# DDS_Out.net
KiCad netlist of a schematic drawn in Altium Designer
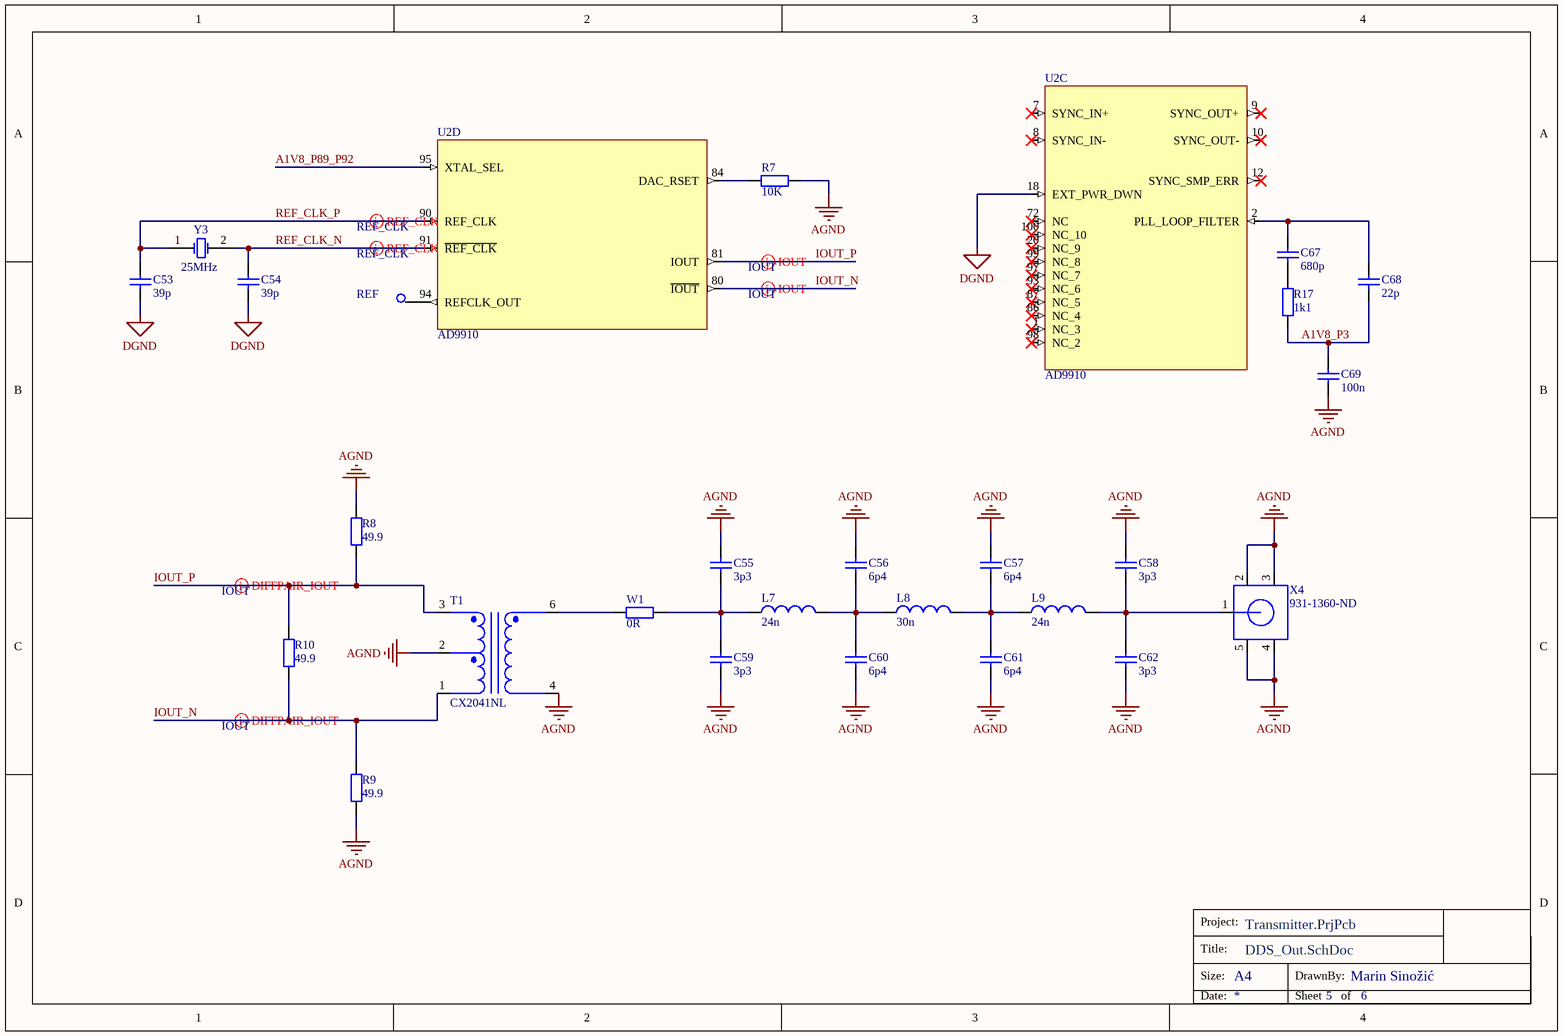
[diagram p0: DDS_Out.SchDoc]

(export (version "E")
  (design (tool "Eeschema 10.0.6"))
  (components
    (comp (ref "C53")
      (value "39p")
      (footprint "0603")
      (description "CAP CER 39PF 50V C0G/NP0 0603")
      (fields (field (name "MANUFACTURER PART NUMBER") "720-VJ0603A390GXACW1BCCT-ND"))
      (libsource (lib "Miscellaneous Devices") (part "Cap"))
    )
    (comp (ref "C54")
      (value "39p")
      (footprint "0603")
      (description "CAP CER 39PF 50V C0G/NP0 0603")
      (fields (field (name "MANUFACTURER PART NUMBER") "720-VJ0603A390GXACW1BCCT-ND"))
      (libsource (lib "Miscellaneous Devices") (part "Cap"))
    )
    (comp (ref "C55")
      (value "3p3")
      (footprint "0603")
      (description "CAP CER 3.3PF 50V C0G/NPO 0603")
      (fields (field (name "MANUFACTURER PART NUMBER") "311-3832-1-ND"))
      (libsource (lib "Tx_board") (part "C_0402_3.3pF"))
    )
    (comp (ref "C56")
      (value "6p4")
      (footprint "0603")
      (description "CAP CER RF 6.4PF 50V +/-0.1 PF C")
      (fields (field (name "MANUFACTURER PART NUMBER") "399-16225-1-ND"))
      (libsource (lib "Tx_board") (part "C_0402_6.8pF"))
    )
    (comp (ref "C57")
      (value "6p4")
      (footprint "0603")
      (description "CAP CER RF 6.4PF 50V +/-0.1 PF C")
      (fields (field (name "MANUFACTURER PART NUMBER") "399-16225-1-ND"))
      (libsource (lib "Tx_board") (part "C_0402_6.8pF"))
    )
    (comp (ref "C58")
      (value "3p3")
      (footprint "0603")
      (description "CAP CER 3.3PF 50V C0G/NPO 0603")
      (fields (field (name "MANUFACTURER PART NUMBER") "311-3832-1-ND"))
      (libsource (lib "Tx_board") (part "C_0402_3.3pF"))
    )
    (comp (ref "C59")
      (value "3p3")
      (footprint "0603")
      (description "CAP CER 3.3PF 50V C0G/NPO 0603")
      (fields (field (name "MANUFACTURER PART NUMBER") "311-3832-1-ND"))
      (libsource (lib "Tx_board") (part "C_0402_3.3pF"))
    )
    (comp (ref "C60")
      (value "6p4")
      (footprint "0603")
      (description "CAP CER RF 6.4PF 50V +/-0.1 PF C")
      (fields (field (name "MANUFACTURER PART NUMBER") "399-16225-1-ND"))
      (libsource (lib "Tx_board") (part "C_0402_6.8pF"))
    )
    (comp (ref "C61")
      (value "6p4")
      (footprint "0603")
      (description "CAP CER RF 6.4PF 50V +/-0.1 PF C")
      (fields (field (name "MANUFACTURER PART NUMBER") "399-16225-1-ND"))
      (libsource (lib "Tx_board") (part "C_0402_6.8pF"))
    )
    (comp (ref "C62")
      (value "3p3")
      (footprint "0603")
      (description "CAP CER 3.3PF 50V C0G/NPO 0603")
      (fields (field (name "MANUFACTURER PART NUMBER") "311-3832-1-ND"))
      (libsource (lib "Tx_board") (part "C_0402_3.3pF"))
    )
    (comp (ref "C67")
      (value "680p")
      (footprint "0603")
      (description "CAP CER RF 6.4PF 50V +/-0.1 PF C")
      (fields (field (name "MANUFACTURER PART NUMBER") "399-16225-1-ND"))
      (libsource (lib "Tx_board") (part "C_0402_6.8pF"))
    )
    (comp (ref "C68")
      (value "22p")
      (footprint "0603")
      (description "CAP CER RF 6.4PF 50V +/-0.1 PF C")
      (fields (field (name "MANUFACTURER PART NUMBER") "399-16225-1-ND"))
      (libsource (lib "Tx_board") (part "C_0402_6.8pF"))
    )
    (comp (ref "C69")
      (value "100n")
      (footprint "0603")
      (description "CAP CER RF 6.4PF 50V +/-0.1 PF C")
      (fields (field (name "MANUFACTURER PART NUMBER") "399-16225-1-ND"))
      (libsource (lib "Tx_board") (part "C_0402_6.8pF"))
    )
    (comp (ref "L7")
      (value "24n")
      (footprint "0603")
      (description "FIXED IND 24NH 500MA 210MOHM SMD")
      (fields (field (name "MANUFACTURER PART NUMBER") "490-6877-1-ND"))
      (libsource (lib "Tx_board") (part "L_0402_24nH"))
    )
    (comp (ref "L8")
      (value "30n")
      (footprint "0603")
      (description "FIXED IND 30NH 600MA 144MOHM SMD")
      (fields (field (name "MANUFACTURER PART NUMBER") "490-15816-1-ND"))
      (libsource (lib "Tx_board") (part "L_0402_30nH"))
    )
    (comp (ref "L9")
      (value "24n")
      (footprint "0603")
      (description "FIXED IND 24NH 500MA 210MOHM SMD")
      (fields (field (name "MANUFACTURER PART NUMBER") "490-6877-1-ND"))
      (libsource (lib "Tx_board") (part "L_0402_24nH"))
    )
    (comp (ref "R7")
      (value "10K")
      (footprint "0603")
      (description "RES SMD 10K OHM 0.5% 1/5W 0603")
      (fields (field (name "MANUFACTURER PART NUMBER") "P20397CT-ND"))
      (libsource (lib "") (part "Res2_1"))
    )
    (comp (ref "R8")
      (value "49.9")
      (footprint "0805")
      (description "RES SMD 49.9 OHM 0.1% 1/10W 0603")
      (fields (field (name "MANUFACTURER PART NUMBER") "P49.9DBCT-ND"))
      (libsource (lib "Miscellaneous Devices") (part "Res2"))
    )
    (comp (ref "R9")
      (value "49.9")
      (footprint "0805")
      (description "RES SMD 49.9 OHM 0.1% 1/10W 0603")
      (fields (field (name "MANUFACTURER PART NUMBER") "P49.9DBCT-ND"))
      (libsource (lib "Miscellaneous Devices") (part "Res2"))
    )
    (comp (ref "R10")
      (value "49.9")
      (footprint "0805")
      (description "RES SMD 49.9 OHM 0.1% 1/10W 0603")
      (fields (field (name "MANUFACTURER PART NUMBER") "P49.9DBCT-ND"))
      (libsource (lib "Miscellaneous Devices") (part "Res2"))
    )
    (comp (ref "R17")
      (value "TBD")
      (footprint "0603")
      (description "RES SMD 0 OHM JUMPER 1/3W 0603")
      (fields (field (name "MANUFACTURER PART NUMBER") "541-0.0SBCT-ND") (field (name "RESISTANCE") "1k1"))
      (libsource (lib "") (part "R_0603_0ohm_1"))
    )
    (comp (ref "REF") (value "TestPoint") (footprint "TP") (libsource (lib "Transmitter") (part "TestPoint")))
    (comp (ref "T1")
      (value "CX2041NL")
      (footprint "RF_TRANSF")
      (description "BALUN 50KHZ-450MHZ 75/75 5SMD")
      (fields (field (name "MANUFACTURER PART NUMBER") "553-3187-ND"))
      (libsource (lib "Tx_board") (part "RF_TRANSF"))
    )
    (comp (ref "U2")
      (value "AD9910")
      (footprint "TSQFP50P1600X1600X105_HS-101N")
      (description "ANALOG DEVICES - AD9910BSVZ - Direct Digital Synthesizer, 1 GSPS. 14 Bit, 3.3 V,")
      (fields (field (name "MANUFACTURER PART NUMBER") "505-AD9910BSVZ-ND"))
      (libsource (lib "Transmitter") (part "AD9910BSVZ"))
    )
    (comp (ref "W1")
      (value "0R")
      (footprint "0603")
      (description "RES SMD 0 OHM JUMPER 1/3W 0603")
      (fields (field (name "MANUFACTURER PART NUMBER") "541-0.0SBCT-ND"))
      (libsource (lib "Tx_board") (part "R_0603_0ohm"))
    )
    (comp (ref "X4")
      (value "931-1360-ND")
      (footprint "SMA")
      (description "CONN RP-SMA JACK R/A 50 OHM PCB")
      (libsource (lib "Tx_board") (part "SMA_JACK"))
    )
    (comp (ref "Y3")
      (value "25MHz")
      (footprint "XTAL_ECS-196-S-23A-TR")
      (description "Crystal 25.0MHZ 20PF SMD")
      (fields (field (name "MANUFACTURER PART NUMBER") "50-ECS-250-20-23A-EN-TRCT-ND"))
      (libsource (lib "Miscellaneous Devices") (part "XTAL"))
    )
  )
  (nets
    (net (code "1") (name "/A1V8_P3") (class "Default")
      (node (ref "C68") (pin "1") (pinfunction "1_1") (pintype "passive"))
      (node (ref "C69") (pin "2") (pinfunction "2_2") (pintype "passive"))
      (node (ref "R17") (pin "2") (pinfunction "2_2") (pintype "passive"))
    )
    (net (code "2") (name "/A1V8_P89_P92") (class "Default")
      (node (ref "U2") (pin "95") (pinfunction "XTAL_SEL_95") (pintype "input"))
    )
    (net (code "3") (name "/IOUT_N") (class "Default")
      (node (ref "R10") (pin "2") (pinfunction "2_2") (pintype "passive"))
      (node (ref "R9") (pin "1") (pinfunction "1_1") (pintype "passive"))
      (node (ref "T1") (pin "1") (pinfunction "1_1") (pintype "passive"))
      (node (ref "U2") (pin "80") (pinfunction "~{IOUT}_80") (pintype "output"))
    )
    (net (code "4") (name "/IOUT_P") (class "Default")
      (node (ref "R10") (pin "1") (pinfunction "1_1") (pintype "passive"))
      (node (ref "R8") (pin "2") (pinfunction "2_2") (pintype "passive"))
      (node (ref "T1") (pin "3") (pinfunction "3_3") (pintype "passive"))
      (node (ref "U2") (pin "81") (pinfunction "IOUT_81") (pintype "output"))
    )
    (net (code "5") (name "/REF_CLK_N") (class "Default")
      (node (ref "C54") (pin "2") (pinfunction "2_2") (pintype "passive"))
      (node (ref "U2") (pin "91") (pinfunction "~{REF_CLK}_91") (pintype "input"))
      (node (ref "Y3") (pin "2") (pinfunction "OSC2_2") (pintype "passive"))
    )
    (net (code "6") (name "/REF_CLK_P") (class "Default")
      (node (ref "C53") (pin "2") (pinfunction "2_2") (pintype "passive"))
      (node (ref "U2") (pin "90") (pinfunction "REF_CLK_90") (pintype "input"))
      (node (ref "Y3") (pin "1") (pinfunction "OSC1_1") (pintype "passive"))
    )
    (net (code "7") (name "AGND") (class "Default")
      (node (ref "C55") (pin "2") (pinfunction "2_2") (pintype "passive"))
      (node (ref "C56") (pin "2") (pinfunction "2_2") (pintype "passive"))
      (node (ref "C57") (pin "2") (pinfunction "2_2") (pintype "passive"))
      (node (ref "C58") (pin "2") (pinfunction "2_2") (pintype "passive"))
      (node (ref "C59") (pin "1") (pinfunction "1_1") (pintype "passive"))
      (node (ref "C60") (pin "1") (pinfunction "1_1") (pintype "passive"))
      (node (ref "C61") (pin "1") (pinfunction "1_1") (pintype "passive"))
      (node (ref "C62") (pin "1") (pinfunction "1_1") (pintype "passive"))
      (node (ref "C69") (pin "1") (pinfunction "1_1") (pintype "passive"))
      (node (ref "R7") (pin "1") (pinfunction "1_1") (pintype "passive"))
      (node (ref "R8") (pin "1") (pinfunction "1_1") (pintype "passive"))
      (node (ref "R9") (pin "2") (pinfunction "2_2") (pintype "passive"))
      (node (ref "T1") (pin "2") (pinfunction "2_2") (pintype "passive"))
      (node (ref "T1") (pin "4") (pinfunction "4_4") (pintype "passive"))
      (node (ref "X4") (pin "2") (pinfunction "GND_2") (pintype "passive"))
      (node (ref "X4") (pin "3") (pinfunction "GND_3") (pintype "passive"))
      (node (ref "X4") (pin "4") (pinfunction "GND_4") (pintype "passive"))
      (node (ref "X4") (pin "5") (pinfunction "GND_5") (pintype "passive"))
    )
    (net (code "8") (name "DGND") (class "Default")
      (node (ref "C53") (pin "1") (pinfunction "1_1") (pintype "passive"))
      (node (ref "C54") (pin "1") (pinfunction "1_1") (pintype "passive"))
      (node (ref "U2") (pin "18") (pinfunction "EXT_PWR_DWN_18") (pintype "input"))
    )
    (net (code "9") (name "Net-(C55-Pad1)") (class "Default")
      (node (ref "C55") (pin "1") (pinfunction "1_1") (pintype "passive"))
      (node (ref "C59") (pin "2") (pinfunction "2_2") (pintype "passive"))
      (node (ref "L7") (pin "1") (pinfunction "1_1") (pintype "passive"))
      (node (ref "W1") (pin "2") (pinfunction "2_2") (pintype "passive"))
    )
    (net (code "10") (name "Net-(C56-Pad1)") (class "Default")
      (node (ref "C56") (pin "1") (pinfunction "1_1") (pintype "passive"))
      (node (ref "C60") (pin "2") (pinfunction "2_2") (pintype "passive"))
      (node (ref "L7") (pin "2") (pinfunction "2_2") (pintype "passive"))
      (node (ref "L8") (pin "1") (pinfunction "1_1") (pintype "passive"))
    )
    (net (code "11") (name "Net-(C57-Pad1)") (class "Default")
      (node (ref "C57") (pin "1") (pinfunction "1_1") (pintype "passive"))
      (node (ref "C61") (pin "2") (pinfunction "2_2") (pintype "passive"))
      (node (ref "L8") (pin "2") (pinfunction "2_2") (pintype "passive"))
      (node (ref "L9") (pin "1") (pinfunction "1_1") (pintype "passive"))
    )
    (net (code "12") (name "Net-(C67-Pad1)") (class "Default")
      (node (ref "C67") (pin "1") (pinfunction "1_1") (pintype "passive"))
      (node (ref "R17") (pin "1") (pinfunction "1_1") (pintype "passive"))
    )
    (net (code "13") (name "Net-(T1-Pad6)") (class "Default")
      (node (ref "T1") (pin "6") (pinfunction "6_6") (pintype "passive"))
      (node (ref "W1") (pin "1") (pinfunction "1_1") (pintype "passive"))
    )
    (net (code "14") (name "Net-(U2C-PLL_LOOP_FILTER)") (class "Default")
      (node (ref "C67") (pin "2") (pinfunction "2_2") (pintype "passive"))
      (node (ref "C68") (pin "2") (pinfunction "2_2") (pintype "passive"))
      (node (ref "U2") (pin "2") (pinfunction "PLL_LOOP_FILTER_2") (pintype "input"))
    )
    (net (code "15") (name "Net-(U2D-DAC_RSET)") (class "Default")
      (node (ref "R7") (pin "2") (pinfunction "2_2") (pintype "passive"))
      (node (ref "U2") (pin "84") (pinfunction "DAC_RSET_84") (pintype "output"))
    )
    (net (code "16") (name "Net-(U2D-REFCLK_OUT)") (class "Default")
      (node (ref "REF") (pin "1") (pintype "passive"))
      (node (ref "U2") (pin "94") (pinfunction "REFCLK_OUT_94") (pintype "output"))
    )
    (net (code "17") (name "Net-(X4-OUT)") (class "Default")
      (node (ref "C58") (pin "1") (pinfunction "1_1") (pintype "passive"))
      (node (ref "C62") (pin "2") (pinfunction "2_2") (pintype "passive"))
      (node (ref "L9") (pin "2") (pinfunction "2_2") (pintype "passive"))
      (node (ref "X4") (pin "1") (pinfunction "OUT_1") (pintype "passive"))
    )
    (net (code "18") (name "unconnected-(U2C-NC-Pad72)") (class "Default")
      (node (ref "U2") (pin "72") (pinfunction "NC_72") (pintype "input+no_connect"))
    )
    (net (code "19") (name "unconnected-(U2C-NC_2-Pad98)") (class "Default")
      (node (ref "U2") (pin "98") (pinfunction "NC_2_98") (pintype "input+no_connect"))
    )
    (net (code "20") (name "unconnected-(U2C-NC_3-Pad1)") (class "Default")
      (node (ref "U2") (pin "1") (pinfunction "NC_3_1") (pintype "input+no_connect"))
    )
    (net (code "21") (name "unconnected-(U2C-NC_4-Pad86)") (class "Default")
      (node (ref "U2") (pin "86") (pinfunction "NC_4_86") (pintype "input+no_connect"))
    )
    (net (code "22") (name "unconnected-(U2C-NC_5-Pad87)") (class "Default")
      (node (ref "U2") (pin "87") (pinfunction "NC_5_87") (pintype "input+no_connect"))
    )
    (net (code "23") (name "unconnected-(U2C-NC_6-Pad93)") (class "Default")
      (node (ref "U2") (pin "93") (pinfunction "NC_6_93") (pintype "input+no_connect"))
    )
    (net (code "24") (name "unconnected-(U2C-NC_7-Pad97)") (class "Default")
      (node (ref "U2") (pin "97") (pinfunction "NC_7_97") (pintype "input+no_connect"))
    )
    (net (code "25") (name "unconnected-(U2C-NC_8-Pad99)") (class "Default")
      (node (ref "U2") (pin "99") (pinfunction "NC_8_99") (pintype "input+no_connect"))
    )
    (net (code "26") (name "unconnected-(U2C-NC_9-Pad20)") (class "Default")
      (node (ref "U2") (pin "20") (pinfunction "NC_9_20") (pintype "input+no_connect"))
    )
    (net (code "27") (name "unconnected-(U2C-NC_10-Pad100)") (class "Default")
      (node (ref "U2") (pin "100") (pinfunction "NC_10_100") (pintype "input+no_connect"))
    )
    (net (code "28") (name "unconnected-(U2C-SYNC_IN+-Pad7)") (class "Default")
      (node (ref "U2") (pin "7") (pinfunction "SYNC_IN+_7") (pintype "input+no_connect"))
    )
    (net (code "29") (name "unconnected-(U2C-SYNC_IN--Pad8)") (class "Default")
      (node (ref "U2") (pin "8") (pinfunction "SYNC_IN-_8") (pintype "input+no_connect"))
    )
    (net (code "30") (name "unconnected-(U2C-SYNC_OUT+-Pad9)") (class "Default")
      (node (ref "U2") (pin "9") (pinfunction "SYNC_OUT+_9") (pintype "output+no_connect"))
    )
    (net (code "31") (name "unconnected-(U2C-SYNC_OUT--Pad10)") (class "Default")
      (node (ref "U2") (pin "10") (pinfunction "SYNC_OUT-_10") (pintype "output+no_connect"))
    )
    (net (code "32") (name "unconnected-(U2C-SYNC_SMP_ERR-Pad12)") (class "Default")
      (node (ref "U2") (pin "12") (pinfunction "SYNC_SMP_ERR_12") (pintype "output+no_connect"))
    )
  )
)
